# schema.net
KiCad netlist of a schematic drawn in EAGLE
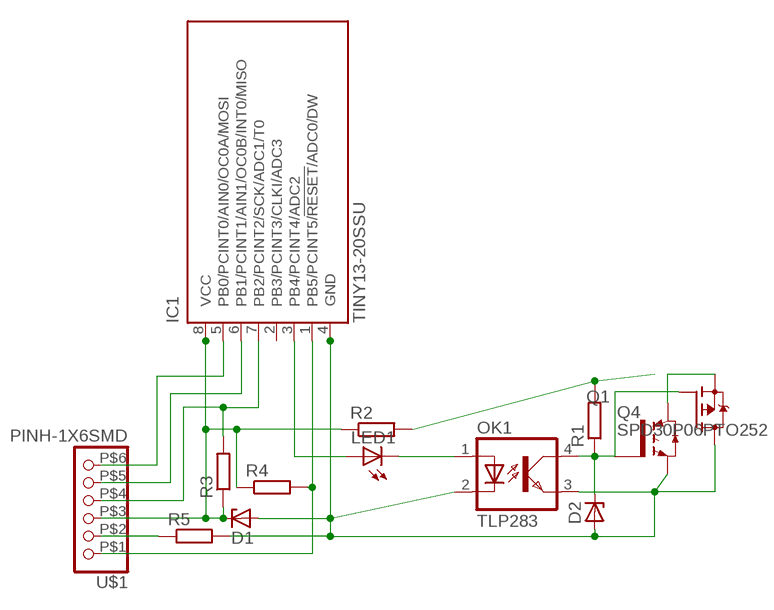
[diagram p0: schematic, sheet 1]

(export (version "E")
  (design (tool "Eeschema 10.0.6"))
  (components
    (comp (ref "D1")
      (value "ZENER-DIODESOD80C")
      (footprint "eagle-import:SOD80C")
      (libsource (lib "eagle-import") (part "ZENER-DIODESOD80C"))
    )
    (comp (ref "D2")
      (value "ZENER-DIODESOD80C")
      (footprint "eagle-import:SOD80C")
      (libsource (lib "eagle-import") (part "ZENER-DIODESOD80C"))
    )
    (comp (ref "IC1")
      (value "TINY13-20SSU")
      (footprint "eagle-import:8S1")
      (fields (field (name "MPN") "ATTINY13-20SSU"))
      (libsource (lib "eagle-import") (part "TINY13SSU-20"))
    )
    (comp (ref "LED1")
      (value "LEDSML1206")
      (footprint "eagle-import:SML1206")
      (libsource (lib "eagle-import") (part "LEDSML1206"))
    )
    (comp (ref "OK1")
      (value "TLP283")
      (footprint "eagle-import:MINI-FLAT-4")
      (libsource (lib "eagle-import") (part "TLP283"))
    )
    (comp (ref "Q1")
      (value "IRG4BC15UD-S")
      (footprint "eagle-import:D2PACK")
      (libsource (lib "eagle-import") (part "IRG4BC15UD-S"))
    )
    (comp (ref "Q4")
      (value "SPD30P06PTO252")
      (footprint "eagle-import:TO252")
      (libsource (lib "eagle-import") (part "SPD30P06PTO252"))
    )
    (comp (ref "R1")
      (value "R-EU_R1206")
      (footprint "eagle-import:R1206")
      (libsource (lib "eagle-import") (part "R-EU_R1206"))
    )
    (comp (ref "R2")
      (value "R-EU_R1206")
      (footprint "eagle-import:R1206")
      (libsource (lib "eagle-import") (part "R-EU_R1206"))
    )
    (comp (ref "R3")
      (value "R-EU_R1206")
      (footprint "eagle-import:R1206")
      (libsource (lib "eagle-import") (part "R-EU_R1206"))
    )
    (comp (ref "R4")
      (value "R-EU_R1206")
      (footprint "eagle-import:R1206")
      (libsource (lib "eagle-import") (part "R-EU_R1206"))
    )
    (comp (ref "R5")
      (value "R-EU_R1206")
      (footprint "eagle-import:R1206")
      (libsource (lib "eagle-import") (part "R-EU_R1206"))
    )
    (comp (ref "U$1")
      (value "PINH-1X6SMD")
      (footprint "eagle-import:1X06_90SMD")
      (libsource (lib "eagle-import") (part "PINH-1X6SMD"))
    )
  )
  (nets
    (net (code "1") (name "Net-(IC1-GND)") (class "Default")
      (node (ref "D1") (pin "A") (pinfunction "A_A") (pintype "passive"))
      (node (ref "D2") (pin "A") (pinfunction "A_A") (pintype "passive"))
      (node (ref "IC1") (pin "4") (pinfunction "GND_4") (pintype "power_in"))
      (node (ref "OK1") (pin "2") (pinfunction "C_2") (pintype "passive"))
      (node (ref "OK1") (pin "3") (pinfunction "EMIT_3") (pintype "passive"))
      (node (ref "Q1") (pin "3") (pinfunction "E_3") (pintype "passive"))
      (node (ref "Q4") (pin "3") (pinfunction "D_3") (pintype "passive"))
      (node (ref "R5") (pin "2") (pinfunction "2_2") (pintype "passive"))
    )
    (net (code "2") (name "Net-(IC1-PB0{slash}PCINT0{slash}AIN0{slash}OC0A{slash}MOSI)") (class "Default")
      (node (ref "IC1") (pin "5") (pinfunction "PB0/PCINT0/AIN0/OC0A/MOSI_5") (pintype "bidirectional"))
      (node (ref "U$1") (pin "P$6") (pinfunction "6_P$6") (pintype "passive"))
    )
    (net (code "3") (name "Net-(IC1-PB1{slash}PCINT1{slash}AIN1{slash}OC0B{slash}INT0{slash}MISO)") (class "Default")
      (node (ref "IC1") (pin "6") (pinfunction "PB1/PCINT1/AIN1/OC0B/INT0/MISO_6") (pintype "bidirectional"))
      (node (ref "U$1") (pin "P$5") (pinfunction "5_P$5") (pintype "passive"))
    )
    (net (code "4") (name "Net-(IC1-PB2{slash}PCINT2{slash}SCK{slash}ADC1{slash}T0)") (class "Default")
      (node (ref "IC1") (pin "7") (pinfunction "PB2/PCINT2/SCK/ADC1/T0_7") (pintype "bidirectional"))
      (node (ref "R3") (pin "2") (pinfunction "2_2") (pintype "passive"))
      (node (ref "U$1") (pin "P$4") (pinfunction "4_P$4") (pintype "passive"))
    )
    (net (code "5") (name "Net-(IC1-PB4{slash}PCINT4{slash}ADC2)") (class "Default")
      (node (ref "IC1") (pin "3") (pinfunction "PB4/PCINT4/ADC2_3") (pintype "bidirectional"))
      (node (ref "LED1") (pin "A") (pinfunction "A_A") (pintype "passive"))
    )
    (net (code "6") (name "Net-(IC1-PB5{slash}PCINT5{slash}~{RESET}{slash}ADC0{slash}DW)") (class "Default")
      (node (ref "IC1") (pin "1") (pinfunction "PB5/PCINT5/~{RESET}/ADC0/DW_1") (pintype "bidirectional"))
      (node (ref "R4") (pin "2") (pinfunction "2_2") (pintype "passive"))
      (node (ref "U$1") (pin "P$1") (pinfunction "1_P$1") (pintype "passive"))
    )
    (net (code "7") (name "Net-(IC1-VCC)") (class "Default")
      (node (ref "D1") (pin "C") (pinfunction "C_C") (pintype "passive"))
      (node (ref "IC1") (pin "8") (pinfunction "VCC_8") (pintype "power_in"))
      (node (ref "R2") (pin "1") (pinfunction "1_1") (pintype "passive"))
      (node (ref "R3") (pin "1") (pinfunction "1_1") (pintype "passive"))
      (node (ref "R4") (pin "1") (pinfunction "1_1") (pintype "passive"))
      (node (ref "U$1") (pin "P$3") (pinfunction "3_P$3") (pintype "passive"))
    )
    (net (code "8") (name "Net-(OK1-A)") (class "Default")
      (node (ref "LED1") (pin "C") (pinfunction "C_C") (pintype "passive"))
      (node (ref "OK1") (pin "1") (pinfunction "A_1") (pintype "passive"))
    )
    (net (code "9") (name "Net-(OK1-COL)") (class "Default")
      (node (ref "D2") (pin "C") (pinfunction "C_C") (pintype "passive"))
      (node (ref "OK1") (pin "4") (pinfunction "COL_4") (pintype "passive"))
      (node (ref "Q1") (pin "1") (pinfunction "G_1") (pintype "passive"))
      (node (ref "Q4") (pin "1") (pinfunction "G_1") (pintype "passive"))
      (node (ref "R1") (pin "1") (pinfunction "1_1") (pintype "passive"))
    )
    (net (code "10") (name "Net-(Q1-C)") (class "Default")
      (node (ref "Q1") (pin "2") (pinfunction "C_2") (pintype "passive"))
      (node (ref "Q4") (pin "2") (pinfunction "S_2") (pintype "passive"))
    )
    (net (code "11") (name "Net-(R1-Pad2)") (class "Default")
      (node (ref "R1") (pin "2") (pinfunction "2_2") (pintype "passive"))
      (node (ref "R2") (pin "2") (pinfunction "2_2") (pintype "passive"))
    )
    (net (code "12") (name "Net-(U$1-2)") (class "Default")
      (node (ref "R5") (pin "1") (pinfunction "1_1") (pintype "passive"))
      (node (ref "U$1") (pin "P$2") (pinfunction "2_P$2") (pintype "passive"))
    )
    (net (code "13") (name "unconnected-(IC1-PB3{slash}PCINT3{slash}CLKI{slash}ADC3-Pad2)") (class "Default")
      (node (ref "IC1") (pin "2") (pinfunction "PB3/PCINT3/CLKI/ADC3_2") (pintype "bidirectional"))
    )
  )
)
